# power-control.net
KiCad netlist of a schematic drawn in EAGLE
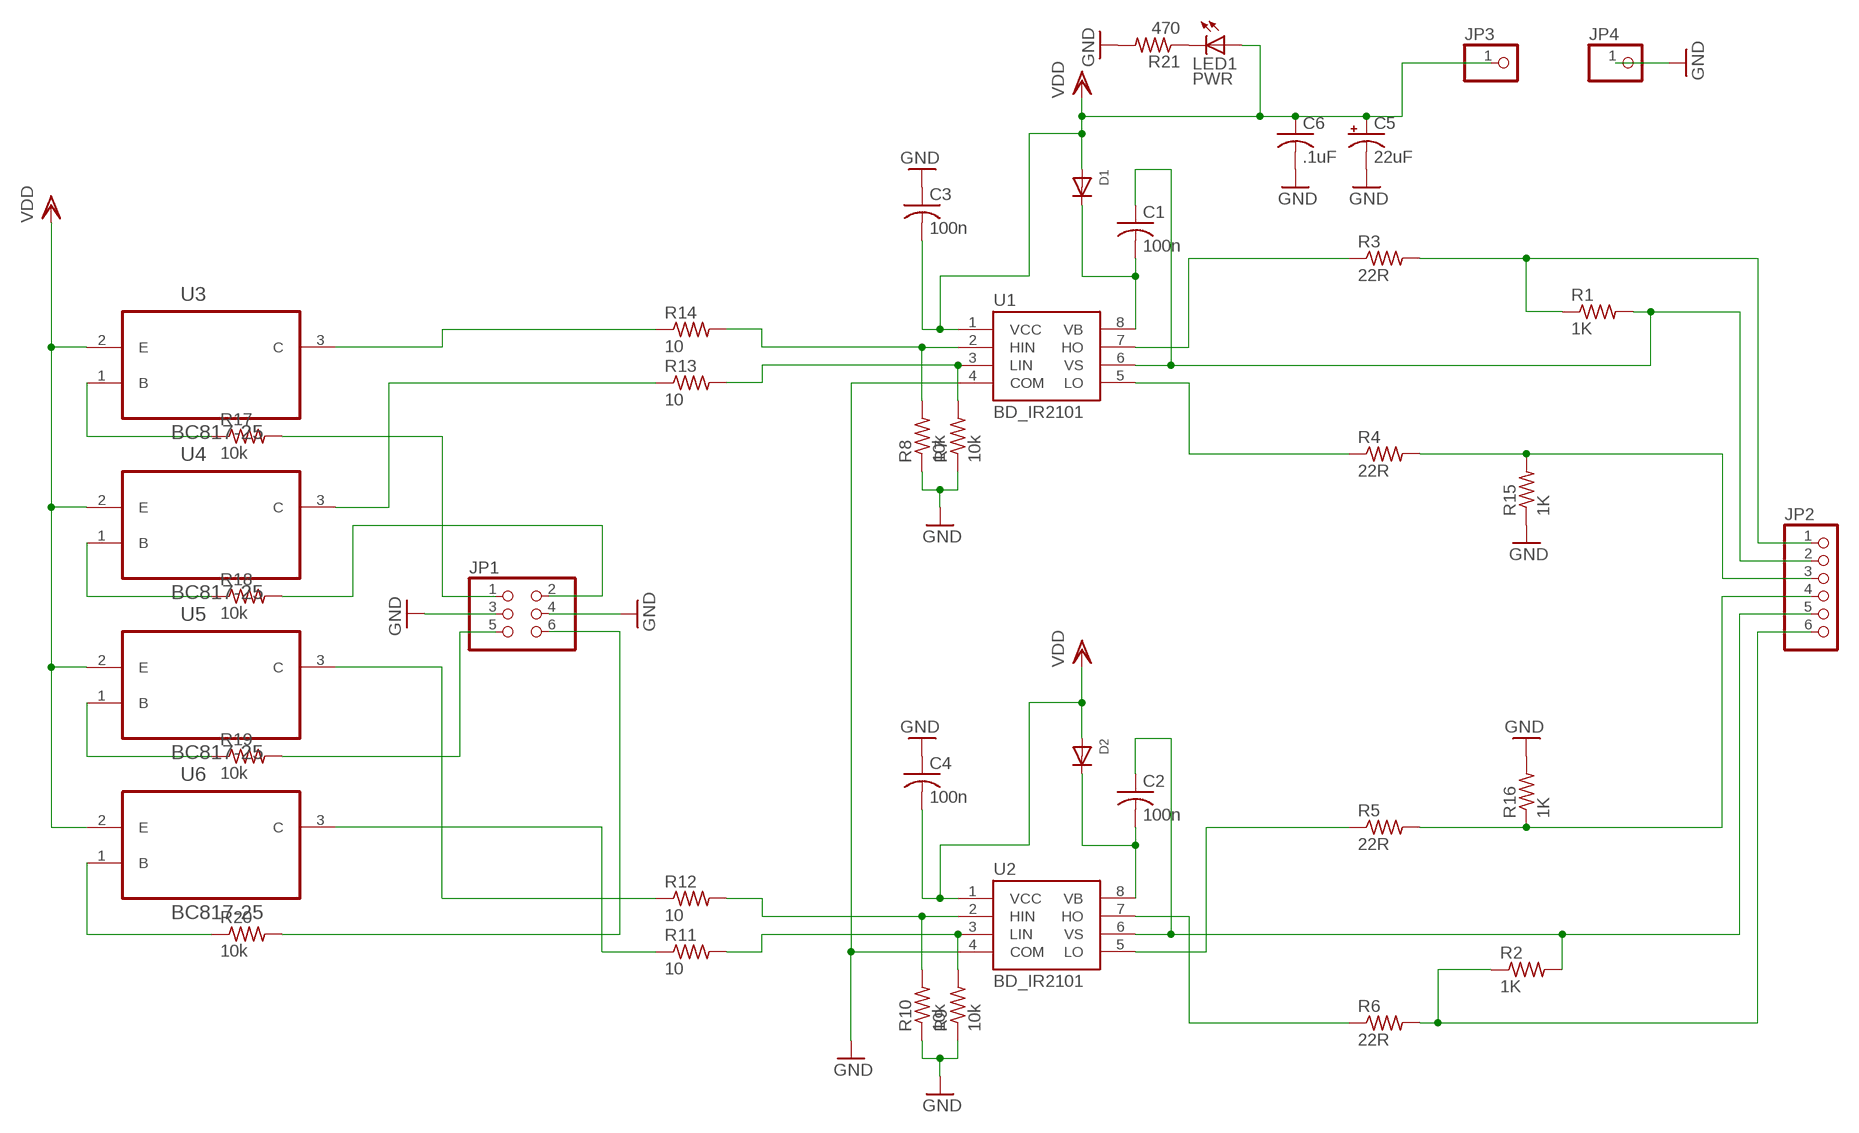
[diagram p0: schematic, sheet 1]

(export (version "E")
  (design (tool "Eeschema 10.0.6"))
  (components
    (comp (ref "C1")
      (value "100n")
      (footprint "eagle-import:C0402")
      (libsource (lib "eagle-import") (part "C-USC0402"))
    )
    (comp (ref "C2")
      (value "100n")
      (footprint "eagle-import:C0402")
      (libsource (lib "eagle-import") (part "C-USC0402"))
    )
    (comp (ref "C3")
      (value "100n")
      (footprint "eagle-import:C0402")
      (libsource (lib "eagle-import") (part "C-USC0402"))
    )
    (comp (ref "C4")
      (value "100n")
      (footprint "eagle-import:C0402")
      (libsource (lib "eagle-import") (part "C-USC0402"))
    )
    (comp (ref "C5")
      (value "22uF")
      (footprint "eagle-import:B_3528-21W")
      (libsource (lib "eagle-import") (part "CPOL-USB/3528-21W"))
    )
    (comp (ref "C6")
      (value ".1uF")
      (footprint "eagle-import:C0805")
      (libsource (lib "eagle-import") (part "C-USC0805"))
    )
    (comp (ref "D1")
      (value "DIODESOD-523")
      (footprint "eagle-import:SOD-523")
      (libsource (lib "eagle-import") (part "DIODESOD-523"))
    )
    (comp (ref "D2")
      (value "DIODESOD-523")
      (footprint "eagle-import:SOD-523")
      (libsource (lib "eagle-import") (part "DIODESOD-523"))
    )
    (comp (ref "JP1")
      (value "PINHD-2X3")
      (footprint "eagle-import:2X03")
      (libsource (lib "eagle-import") (part "PINHD-2X3"))
    )
    (comp (ref "JP2")
      (value "PINHD-1X6")
      (footprint "eagle-import:1X06")
      (libsource (lib "eagle-import") (part "PINHD-1X6"))
    )
    (comp (ref "JP3")
      (value "PINHD-1X1")
      (footprint "eagle-import:1X01")
      (libsource (lib "eagle-import") (part "PINHD-1X1"))
    )
    (comp (ref "JP4")
      (value "PINHD-1X1")
      (footprint "eagle-import:1X01")
      (libsource (lib "eagle-import") (part "PINHD-1X1"))
    )
    (comp (ref "LED1")
      (value "PWR")
      (footprint "eagle-import:CHIP-LED0805")
      (libsource (lib "eagle-import") (part "LEDCHIP-LED0805"))
    )
    (comp (ref "R1")
      (value "1K")
      (footprint "eagle-import:R0201")
      (libsource (lib "eagle-import") (part "R-US_R0201"))
    )
    (comp (ref "R2")
      (value "1K")
      (footprint "eagle-import:R0201")
      (libsource (lib "eagle-import") (part "R-US_R0201"))
    )
    (comp (ref "R3")
      (value "22R")
      (footprint "eagle-import:R0201")
      (libsource (lib "eagle-import") (part "R-US_R0201"))
    )
    (comp (ref "R4")
      (value "22R")
      (footprint "eagle-import:R0201")
      (libsource (lib "eagle-import") (part "R-US_R0201"))
    )
    (comp (ref "R5")
      (value "22R")
      (footprint "eagle-import:R0201")
      (libsource (lib "eagle-import") (part "R-US_R0201"))
    )
    (comp (ref "R6")
      (value "22R")
      (footprint "eagle-import:R0201")
      (libsource (lib "eagle-import") (part "R-US_R0201"))
    )
    (comp (ref "R7")
      (value "10k")
      (footprint "eagle-import:R0201")
      (libsource (lib "eagle-import") (part "R-US_R0201"))
    )
    (comp (ref "R8")
      (value "10k")
      (footprint "eagle-import:R0201")
      (libsource (lib "eagle-import") (part "R-US_R0201"))
    )
    (comp (ref "R9")
      (value "10k")
      (footprint "eagle-import:R0201")
      (libsource (lib "eagle-import") (part "R-US_R0201"))
    )
    (comp (ref "R10")
      (value "10k")
      (footprint "eagle-import:R0201")
      (libsource (lib "eagle-import") (part "R-US_R0201"))
    )
    (comp (ref "R11")
      (value "10")
      (footprint "eagle-import:R0201")
      (libsource (lib "eagle-import") (part "R-US_R0201"))
    )
    (comp (ref "R12")
      (value "10")
      (footprint "eagle-import:R0201")
      (libsource (lib "eagle-import") (part "R-US_R0201"))
    )
    (comp (ref "R13")
      (value "10")
      (footprint "eagle-import:R0201")
      (libsource (lib "eagle-import") (part "R-US_R0201"))
    )
    (comp (ref "R14")
      (value "10")
      (footprint "eagle-import:R0201")
      (libsource (lib "eagle-import") (part "R-US_R0201"))
    )
    (comp (ref "R15")
      (value "1K")
      (footprint "eagle-import:R0201")
      (libsource (lib "eagle-import") (part "R-US_R0201"))
    )
    (comp (ref "R16")
      (value "1K")
      (footprint "eagle-import:R0201")
      (libsource (lib "eagle-import") (part "R-US_R0201"))
    )
    (comp (ref "R17")
      (value "10k")
      (footprint "eagle-import:R0201")
      (libsource (lib "eagle-import") (part "R-US_R0201"))
    )
    (comp (ref "R18")
      (value "10k")
      (footprint "eagle-import:R0201")
      (libsource (lib "eagle-import") (part "R-US_R0201"))
    )
    (comp (ref "R19")
      (value "10k")
      (footprint "eagle-import:R0201")
      (libsource (lib "eagle-import") (part "R-US_R0201"))
    )
    (comp (ref "R20")
      (value "10k")
      (footprint "eagle-import:R0201")
      (libsource (lib "eagle-import") (part "R-US_R0201"))
    )
    (comp (ref "R21")
      (value "470")
      (footprint "eagle-import:R0201")
      (libsource (lib "eagle-import") (part "R-US_R0201"))
    )
    (comp (ref "U1")
      (value "BD_IR2101")
      (footprint "eagle-import:SO8")
      (libsource (lib "eagle-import") (part "BD_IR2101"))
    )
    (comp (ref "U2")
      (value "BD_IR2101")
      (footprint "eagle-import:SO8")
      (libsource (lib "eagle-import") (part "BD_IR2101"))
    )
    (comp (ref "U3")
      (value "BC817-25")
      (footprint "eagle-import:SOT95P240X97-3N")
      (libsource (lib "eagle-import") (part "BC817-25"))
    )
    (comp (ref "U4")
      (value "BC817-25")
      (footprint "eagle-import:SOT95P240X97-3N")
      (libsource (lib "eagle-import") (part "BC817-25"))
    )
    (comp (ref "U5")
      (value "BC817-25")
      (footprint "eagle-import:SOT95P240X97-3N")
      (libsource (lib "eagle-import") (part "BC817-25"))
    )
    (comp (ref "U6")
      (value "BC817-25")
      (footprint "eagle-import:SOT95P240X97-3N")
      (libsource (lib "eagle-import") (part "BC817-25"))
    )
  )
  (nets
    (net (code "1") (name "GND") (class "Default")
      (node (ref "C3") (pin "1") (pinfunction "1_1") (pintype "passive"))
      (node (ref "C4") (pin "1") (pinfunction "1_1") (pintype "passive"))
      (node (ref "C5") (pin "-") (pinfunction "-_-") (pintype "passive"))
      (node (ref "C6") (pin "2") (pinfunction "2_2") (pintype "passive"))
      (node (ref "JP1") (pin "3") (pinfunction "3_3") (pintype "passive"))
      (node (ref "JP1") (pin "4") (pinfunction "4_4") (pintype "passive"))
      (node (ref "JP4") (pin "1") (pinfunction "1_1") (pintype "passive"))
      (node (ref "R10") (pin "1") (pinfunction "1_1") (pintype "passive"))
      (node (ref "R15") (pin "1") (pinfunction "1_1") (pintype "passive"))
      (node (ref "R16") (pin "2") (pinfunction "2_2") (pintype "passive"))
      (node (ref "R21") (pin "2") (pinfunction "2_2") (pintype "passive"))
      (node (ref "R7") (pin "1") (pinfunction "1_1") (pintype "passive"))
      (node (ref "R8") (pin "1") (pinfunction "1_1") (pintype "passive"))
      (node (ref "R9") (pin "1") (pinfunction "1_1") (pintype "passive"))
      (node (ref "U1") (pin "4") (pinfunction "COM_4") (pintype "bidirectional"))
      (node (ref "U2") (pin "4") (pinfunction "COM_4") (pintype "bidirectional"))
    )
    (net (code "2") (name "Net-(D1-C)") (class "Default")
      (node (ref "C1") (pin "2") (pinfunction "2_2") (pintype "passive"))
      (node (ref "D1") (pin "K") (pinfunction "C_K") (pintype "passive"))
      (node (ref "U1") (pin "8") (pinfunction "VB_8") (pintype "bidirectional"))
    )
    (net (code "3") (name "Net-(D2-C)") (class "Default")
      (node (ref "C2") (pin "2") (pinfunction "2_2") (pintype "passive"))
      (node (ref "D2") (pin "K") (pinfunction "C_K") (pintype "passive"))
      (node (ref "U2") (pin "8") (pinfunction "VB_8") (pintype "bidirectional"))
    )
    (net (code "4") (name "Net-(JP1-Pad1)") (class "Default")
      (node (ref "JP1") (pin "1") (pinfunction "1_1") (pintype "passive"))
      (node (ref "R17") (pin "2") (pinfunction "2_2") (pintype "passive"))
    )
    (net (code "5") (name "Net-(JP1-Pad2)") (class "Default")
      (node (ref "JP1") (pin "2") (pinfunction "2_2") (pintype "passive"))
      (node (ref "R18") (pin "2") (pinfunction "2_2") (pintype "passive"))
    )
    (net (code "6") (name "Net-(JP1-Pad5)") (class "Default")
      (node (ref "JP1") (pin "5") (pinfunction "5_5") (pintype "passive"))
      (node (ref "R19") (pin "2") (pinfunction "2_2") (pintype "passive"))
    )
    (net (code "7") (name "Net-(JP1-Pad6)") (class "Default")
      (node (ref "JP1") (pin "6") (pinfunction "6_6") (pintype "passive"))
      (node (ref "R20") (pin "2") (pinfunction "2_2") (pintype "passive"))
    )
    (net (code "8") (name "Net-(JP2-Pad1)") (class "Default")
      (node (ref "JP2") (pin "1") (pinfunction "1_1") (pintype "passive"))
      (node (ref "R1") (pin "1") (pinfunction "1_1") (pintype "passive"))
      (node (ref "R3") (pin "2") (pinfunction "2_2") (pintype "passive"))
    )
    (net (code "9") (name "Net-(JP2-Pad3)") (class "Default")
      (node (ref "JP2") (pin "3") (pinfunction "3_3") (pintype "passive"))
      (node (ref "R15") (pin "2") (pinfunction "2_2") (pintype "passive"))
      (node (ref "R4") (pin "2") (pinfunction "2_2") (pintype "passive"))
    )
    (net (code "10") (name "Net-(JP2-Pad4)") (class "Default")
      (node (ref "JP2") (pin "4") (pinfunction "4_4") (pintype "passive"))
      (node (ref "R16") (pin "1") (pinfunction "1_1") (pintype "passive"))
      (node (ref "R5") (pin "2") (pinfunction "2_2") (pintype "passive"))
    )
    (net (code "11") (name "Net-(JP2-Pad6)") (class "Default")
      (node (ref "JP2") (pin "6") (pinfunction "6_6") (pintype "passive"))
      (node (ref "R2") (pin "1") (pinfunction "1_1") (pintype "passive"))
      (node (ref "R6") (pin "2") (pinfunction "2_2") (pintype "passive"))
    )
    (net (code "12") (name "Net-(LED1-PadC)") (class "Default")
      (node (ref "LED1") (pin "C") (pinfunction "C_C") (pintype "passive"))
      (node (ref "R21") (pin "1") (pinfunction "1_1") (pintype "passive"))
    )
    (net (code "13") (name "Net-(U1-HIN)") (class "Default")
      (node (ref "R14") (pin "2") (pinfunction "2_2") (pintype "passive"))
      (node (ref "R8") (pin "2") (pinfunction "2_2") (pintype "passive"))
      (node (ref "U1") (pin "2") (pinfunction "HIN_2") (pintype "bidirectional"))
    )
    (net (code "14") (name "Net-(U1-HO)") (class "Default")
      (node (ref "R3") (pin "1") (pinfunction "1_1") (pintype "passive"))
      (node (ref "U1") (pin "7") (pinfunction "HO_7") (pintype "bidirectional"))
    )
    (net (code "15") (name "Net-(U1-LIN)") (class "Default")
      (node (ref "R13") (pin "2") (pinfunction "2_2") (pintype "passive"))
      (node (ref "R7") (pin "2") (pinfunction "2_2") (pintype "passive"))
      (node (ref "U1") (pin "3") (pinfunction "LIN_3") (pintype "bidirectional"))
    )
    (net (code "16") (name "Net-(U1-LO)") (class "Default")
      (node (ref "R4") (pin "1") (pinfunction "1_1") (pintype "passive"))
      (node (ref "U1") (pin "5") (pinfunction "LO_5") (pintype "bidirectional"))
    )
    (net (code "17") (name "Net-(U1-VS)") (class "Default")
      (node (ref "C1") (pin "1") (pinfunction "1_1") (pintype "passive"))
      (node (ref "JP2") (pin "2") (pinfunction "2_2") (pintype "passive"))
      (node (ref "R1") (pin "2") (pinfunction "2_2") (pintype "passive"))
      (node (ref "U1") (pin "6") (pinfunction "VS_6") (pintype "bidirectional"))
    )
    (net (code "18") (name "Net-(U2-HIN)") (class "Default")
      (node (ref "R10") (pin "2") (pinfunction "2_2") (pintype "passive"))
      (node (ref "R12") (pin "2") (pinfunction "2_2") (pintype "passive"))
      (node (ref "U2") (pin "2") (pinfunction "HIN_2") (pintype "bidirectional"))
    )
    (net (code "19") (name "Net-(U2-HO)") (class "Default")
      (node (ref "R6") (pin "1") (pinfunction "1_1") (pintype "passive"))
      (node (ref "U2") (pin "7") (pinfunction "HO_7") (pintype "bidirectional"))
    )
    (net (code "20") (name "Net-(U2-LIN)") (class "Default")
      (node (ref "R11") (pin "2") (pinfunction "2_2") (pintype "passive"))
      (node (ref "R9") (pin "2") (pinfunction "2_2") (pintype "passive"))
      (node (ref "U2") (pin "3") (pinfunction "LIN_3") (pintype "bidirectional"))
    )
    (net (code "21") (name "Net-(U2-LO)") (class "Default")
      (node (ref "R5") (pin "1") (pinfunction "1_1") (pintype "passive"))
      (node (ref "U2") (pin "5") (pinfunction "LO_5") (pintype "bidirectional"))
    )
    (net (code "22") (name "Net-(U2-VS)") (class "Default")
      (node (ref "C2") (pin "1") (pinfunction "1_1") (pintype "passive"))
      (node (ref "JP2") (pin "5") (pinfunction "5_5") (pintype "passive"))
      (node (ref "R2") (pin "2") (pinfunction "2_2") (pintype "passive"))
      (node (ref "U2") (pin "6") (pinfunction "VS_6") (pintype "bidirectional"))
    )
    (net (code "23") (name "Net-(U3-B)") (class "Default")
      (node (ref "R17") (pin "1") (pinfunction "1_1") (pintype "passive"))
      (node (ref "U3") (pin "1") (pinfunction "B_1") (pintype "passive"))
    )
    (net (code "24") (name "Net-(U3-C)") (class "Default")
      (node (ref "R14") (pin "1") (pinfunction "1_1") (pintype "passive"))
      (node (ref "U3") (pin "3") (pinfunction "C_3") (pintype "passive"))
    )
    (net (code "25") (name "Net-(U4-B)") (class "Default")
      (node (ref "R18") (pin "1") (pinfunction "1_1") (pintype "passive"))
      (node (ref "U4") (pin "1") (pinfunction "B_1") (pintype "passive"))
    )
    (net (code "26") (name "Net-(U4-C)") (class "Default")
      (node (ref "R13") (pin "1") (pinfunction "1_1") (pintype "passive"))
      (node (ref "U4") (pin "3") (pinfunction "C_3") (pintype "passive"))
    )
    (net (code "27") (name "Net-(U5-B)") (class "Default")
      (node (ref "R19") (pin "1") (pinfunction "1_1") (pintype "passive"))
      (node (ref "U5") (pin "1") (pinfunction "B_1") (pintype "passive"))
    )
    (net (code "28") (name "Net-(U5-C)") (class "Default")
      (node (ref "R12") (pin "1") (pinfunction "1_1") (pintype "passive"))
      (node (ref "U5") (pin "3") (pinfunction "C_3") (pintype "passive"))
    )
    (net (code "29") (name "Net-(U6-B)") (class "Default")
      (node (ref "R20") (pin "1") (pinfunction "1_1") (pintype "passive"))
      (node (ref "U6") (pin "1") (pinfunction "B_1") (pintype "passive"))
    )
    (net (code "30") (name "Net-(U6-C)") (class "Default")
      (node (ref "R11") (pin "1") (pinfunction "1_1") (pintype "passive"))
      (node (ref "U6") (pin "3") (pinfunction "C_3") (pintype "passive"))
    )
    (net (code "31") (name "VDD") (class "Default")
      (node (ref "C3") (pin "2") (pinfunction "2_2") (pintype "passive"))
      (node (ref "C4") (pin "2") (pinfunction "2_2") (pintype "passive"))
      (node (ref "C5") (pin "+") (pinfunction "+_+") (pintype "passive"))
      (node (ref "C6") (pin "1") (pinfunction "1_1") (pintype "passive"))
      (node (ref "D1") (pin "A") (pinfunction "A_A") (pintype "passive"))
      (node (ref "D2") (pin "A") (pinfunction "A_A") (pintype "passive"))
      (node (ref "JP3") (pin "1") (pinfunction "1_1") (pintype "passive"))
      (node (ref "LED1") (pin "A") (pinfunction "A_A") (pintype "passive"))
      (node (ref "U1") (pin "1") (pinfunction "VCC_1") (pintype "bidirectional"))
      (node (ref "U2") (pin "1") (pinfunction "VCC_1") (pintype "bidirectional"))
      (node (ref "U3") (pin "2") (pinfunction "E_2") (pintype "passive"))
      (node (ref "U4") (pin "2") (pinfunction "E_2") (pintype "passive"))
      (node (ref "U5") (pin "2") (pinfunction "E_2") (pintype "passive"))
      (node (ref "U6") (pin "2") (pinfunction "E_2") (pintype "passive"))
    )
  )
)
